# Prepherals.net
KiCad netlist of a schematic drawn in Altium Designer
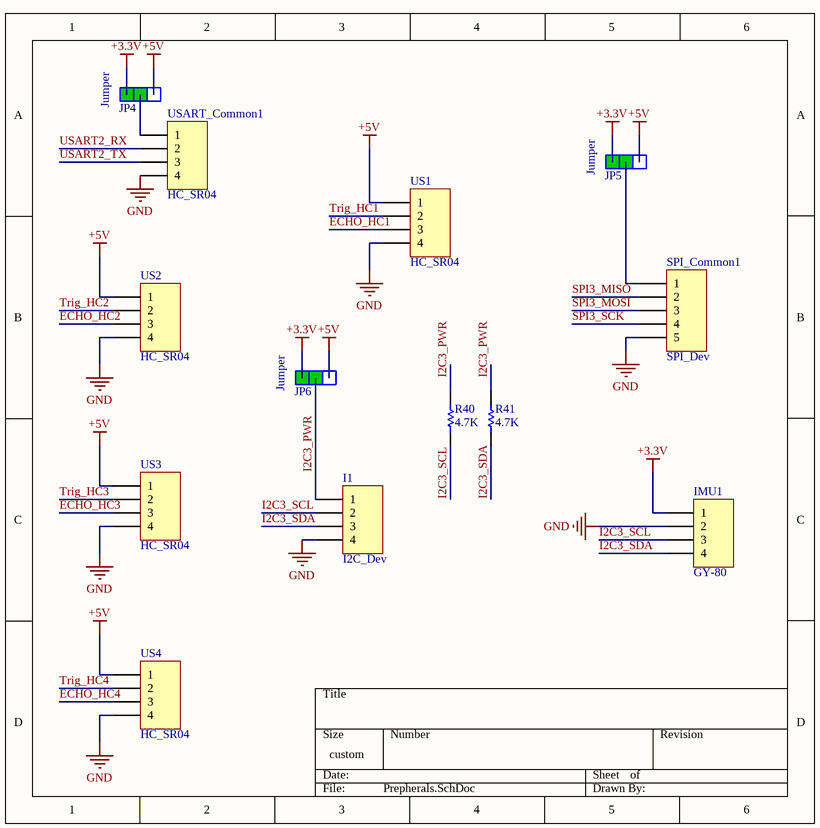
[diagram p0: Prepherals.SchDoc]

(export (version "E")
  (design (tool "Eeschema 10.0.6"))
  (components
    (comp (ref "I1")
      (value "I2C_Dev")
      (footprint "XH Connector 4-Pin")
      (description "Header, 4-Pin Telecom.")
      (fields (field (name "DESIGNER") "Abbas Basereh"))
      (libsource (lib "Altium") (part "Header 4 PIN Telecom."))
    )
    (comp (ref "IMU1")
      (value "GY-80")
      (footprint "XH Connector 4-Pin")
      (description "Header, 4-Pin Telecom.")
      (fields (field (name "DESIGNER") "Abbas Basereh"))
      (libsource (lib "Altium") (part "Header 4 PIN Telecom."))
    )
    (comp (ref "JP4")
      (value "Jumper")
      (footprint "jumper selector")
      (description "Jumper Selector")
      (libsource (lib "Altium") (part "Jumper Selector"))
    )
    (comp (ref "JP5")
      (value "Jumper")
      (footprint "jumper selector")
      (description "Jumper Selector")
      (libsource (lib "Altium") (part "Jumper Selector"))
    )
    (comp (ref "JP6")
      (value "Jumper")
      (footprint "jumper selector")
      (description "Jumper Selector")
      (libsource (lib "Altium") (part "Jumper Selector"))
    )
    (comp (ref "R40")
      (value "4.7K")
      (footprint "RESC3413X04N")
      (description "RES 0805")
      (fields (field (name "DESIGNER") "Abbas Basereh"))
      (libsource (lib "Altium") (part "RES 0805 0.125W"))
    )
    (comp (ref "R41")
      (value "4.7K")
      (footprint "RESC3413X04N")
      (description "RES 0805")
      (fields (field (name "DESIGNER") "Abbas Basereh"))
      (libsource (lib "Altium") (part "RES 0805 0.125W"))
    )
    (comp (ref "SPI_Common1")
      (value "SPI_Dev")
      (footprint "MO-Header 5")
      (description "Header, 5-Pin")
      (fields (field (name "PUBLISHER") "Altium Limited"))
      (libsource (lib "Altium") (part "Header 5"))
    )
    (comp (ref "US1")
      (value "HC_SR04")
      (footprint "XH Connector 4-Pin")
      (description "Header, 4-Pin Telecom.")
      (fields (field (name "DESIGNER") "Abbas Basereh"))
      (libsource (lib "Altium") (part "Header 4 PIN Telecom."))
    )
    (comp (ref "US2")
      (value "HC_SR04")
      (footprint "XH Connector 4-Pin")
      (description "Header, 4-Pin Telecom.")
      (fields (field (name "DESIGNER") "Abbas Basereh"))
      (libsource (lib "Altium") (part "Header 4 PIN Telecom."))
    )
    (comp (ref "US3")
      (value "HC_SR04")
      (footprint "XH Connector 4-Pin")
      (description "Header, 4-Pin Telecom.")
      (fields (field (name "DESIGNER") "Abbas Basereh"))
      (libsource (lib "Altium") (part "Header 4 PIN Telecom."))
    )
    (comp (ref "US4")
      (value "HC_SR04")
      (footprint "XH Connector 4-Pin")
      (description "Header, 4-Pin Telecom.")
      (fields (field (name "DESIGNER") "Abbas Basereh"))
      (libsource (lib "Altium") (part "Header 4 PIN Telecom."))
    )
    (comp (ref "USART_Common1")
      (value "HC_SR04")
      (footprint "XH Connector 4-Pin")
      (description "Header, 4-Pin Telecom.")
      (fields (field (name "DESIGNER") "Abbas Basereh"))
      (libsource (lib "Altium") (part "Header 4 PIN Telecom."))
    )
  )
  (nets
    (net (code "1") (name "+3.3V") (class "Default")
      (node (ref "IMU1") (pin "1") (pinfunction "1_1") (pintype "passive"))
      (node (ref "JP4") (pin "1") (pinfunction "1_1") (pintype "passive"))
      (node (ref "JP5") (pin "1") (pinfunction "1_1") (pintype "passive"))
      (node (ref "JP6") (pin "1") (pinfunction "1_1") (pintype "passive"))
    )
    (net (code "2") (name "+5V") (class "Default")
      (node (ref "JP4") (pin "3") (pinfunction "3_3") (pintype "passive"))
      (node (ref "JP5") (pin "3") (pinfunction "3_3") (pintype "passive"))
      (node (ref "JP6") (pin "3") (pinfunction "3_3") (pintype "passive"))
      (node (ref "US1") (pin "1") (pinfunction "1_1") (pintype "passive"))
      (node (ref "US2") (pin "1") (pinfunction "1_1") (pintype "passive"))
      (node (ref "US3") (pin "1") (pinfunction "1_1") (pintype "passive"))
      (node (ref "US4") (pin "1") (pinfunction "1_1") (pintype "passive"))
    )
    (net (code "3") (name "/ECHO_HC1") (class "Default")
      (node (ref "US1") (pin "3") (pinfunction "3_3") (pintype "passive"))
    )
    (net (code "4") (name "/ECHO_HC2") (class "Default")
      (node (ref "US2") (pin "3") (pinfunction "3_3") (pintype "passive"))
    )
    (net (code "5") (name "/ECHO_HC3") (class "Default")
      (node (ref "US3") (pin "3") (pinfunction "3_3") (pintype "passive"))
    )
    (net (code "6") (name "/ECHO_HC4") (class "Default")
      (node (ref "US4") (pin "3") (pinfunction "3_3") (pintype "passive"))
    )
    (net (code "7") (name "/I2C3_PWR") (class "Default")
      (node (ref "I1") (pin "1") (pinfunction "1_1") (pintype "passive"))
      (node (ref "JP6") (pin "2") (pinfunction "2_2") (pintype "passive"))
      (node (ref "R40") (pin "2") (pinfunction "2_2") (pintype "passive"))
      (node (ref "R41") (pin "2") (pinfunction "2_2") (pintype "passive"))
    )
    (net (code "8") (name "/I2C3_SCL") (class "Default")
      (node (ref "I1") (pin "2") (pinfunction "2_2") (pintype "passive"))
      (node (ref "IMU1") (pin "3") (pinfunction "3_3") (pintype "passive"))
      (node (ref "R40") (pin "1") (pinfunction "1_1") (pintype "passive"))
    )
    (net (code "9") (name "/I2C3_SDA") (class "Default")
      (node (ref "I1") (pin "3") (pinfunction "3_3") (pintype "passive"))
      (node (ref "IMU1") (pin "4") (pinfunction "4_4") (pintype "passive"))
      (node (ref "R41") (pin "1") (pinfunction "1_1") (pintype "passive"))
    )
    (net (code "10") (name "/SPI3_MISO") (class "Default")
      (node (ref "SPI_Common1") (pin "2") (pinfunction "2_2") (pintype "passive"))
    )
    (net (code "11") (name "/SPI3_MOSI") (class "Default")
      (node (ref "SPI_Common1") (pin "3") (pinfunction "3_3") (pintype "passive"))
    )
    (net (code "12") (name "/SPI3_SCK") (class "Default")
      (node (ref "SPI_Common1") (pin "4") (pinfunction "4_4") (pintype "passive"))
    )
    (net (code "13") (name "/Trig_HC1") (class "Default")
      (node (ref "US1") (pin "2") (pinfunction "2_2") (pintype "passive"))
    )
    (net (code "14") (name "/Trig_HC2") (class "Default")
      (node (ref "US2") (pin "2") (pinfunction "2_2") (pintype "passive"))
    )
    (net (code "15") (name "/Trig_HC3") (class "Default")
      (node (ref "US3") (pin "2") (pinfunction "2_2") (pintype "passive"))
    )
    (net (code "16") (name "/Trig_HC4") (class "Default")
      (node (ref "US4") (pin "2") (pinfunction "2_2") (pintype "passive"))
    )
    (net (code "17") (name "/USART2_RX") (class "Default")
      (node (ref "USART_Common1") (pin "2") (pinfunction "2_2") (pintype "passive"))
    )
    (net (code "18") (name "/USART2_TX") (class "Default")
      (node (ref "USART_Common1") (pin "3") (pinfunction "3_3") (pintype "passive"))
    )
    (net (code "19") (name "GND") (class "Default")
      (node (ref "I1") (pin "4") (pinfunction "4_4") (pintype "passive"))
      (node (ref "IMU1") (pin "2") (pinfunction "2_2") (pintype "passive"))
      (node (ref "SPI_Common1") (pin "5") (pinfunction "5_5") (pintype "passive"))
      (node (ref "US1") (pin "4") (pinfunction "4_4") (pintype "passive"))
      (node (ref "US2") (pin "4") (pinfunction "4_4") (pintype "passive"))
      (node (ref "US3") (pin "4") (pinfunction "4_4") (pintype "passive"))
      (node (ref "US4") (pin "4") (pinfunction "4_4") (pintype "passive"))
      (node (ref "USART_Common1") (pin "4") (pinfunction "4_4") (pintype "passive"))
    )
    (net (code "20") (name "Net-(JP4-Pad2)") (class "Default")
      (node (ref "JP4") (pin "2") (pinfunction "2_2") (pintype "passive"))
      (node (ref "USART_Common1") (pin "1") (pinfunction "1_1") (pintype "passive"))
    )
    (net (code "21") (name "Net-(JP5-Pad2)") (class "Default")
      (node (ref "JP5") (pin "2") (pinfunction "2_2") (pintype "passive"))
      (node (ref "SPI_Common1") (pin "1") (pinfunction "1_1") (pintype "passive"))
    )
  )
)
